# base_circuit.net
KiCad netlist of a schematic drawn in EAGLE
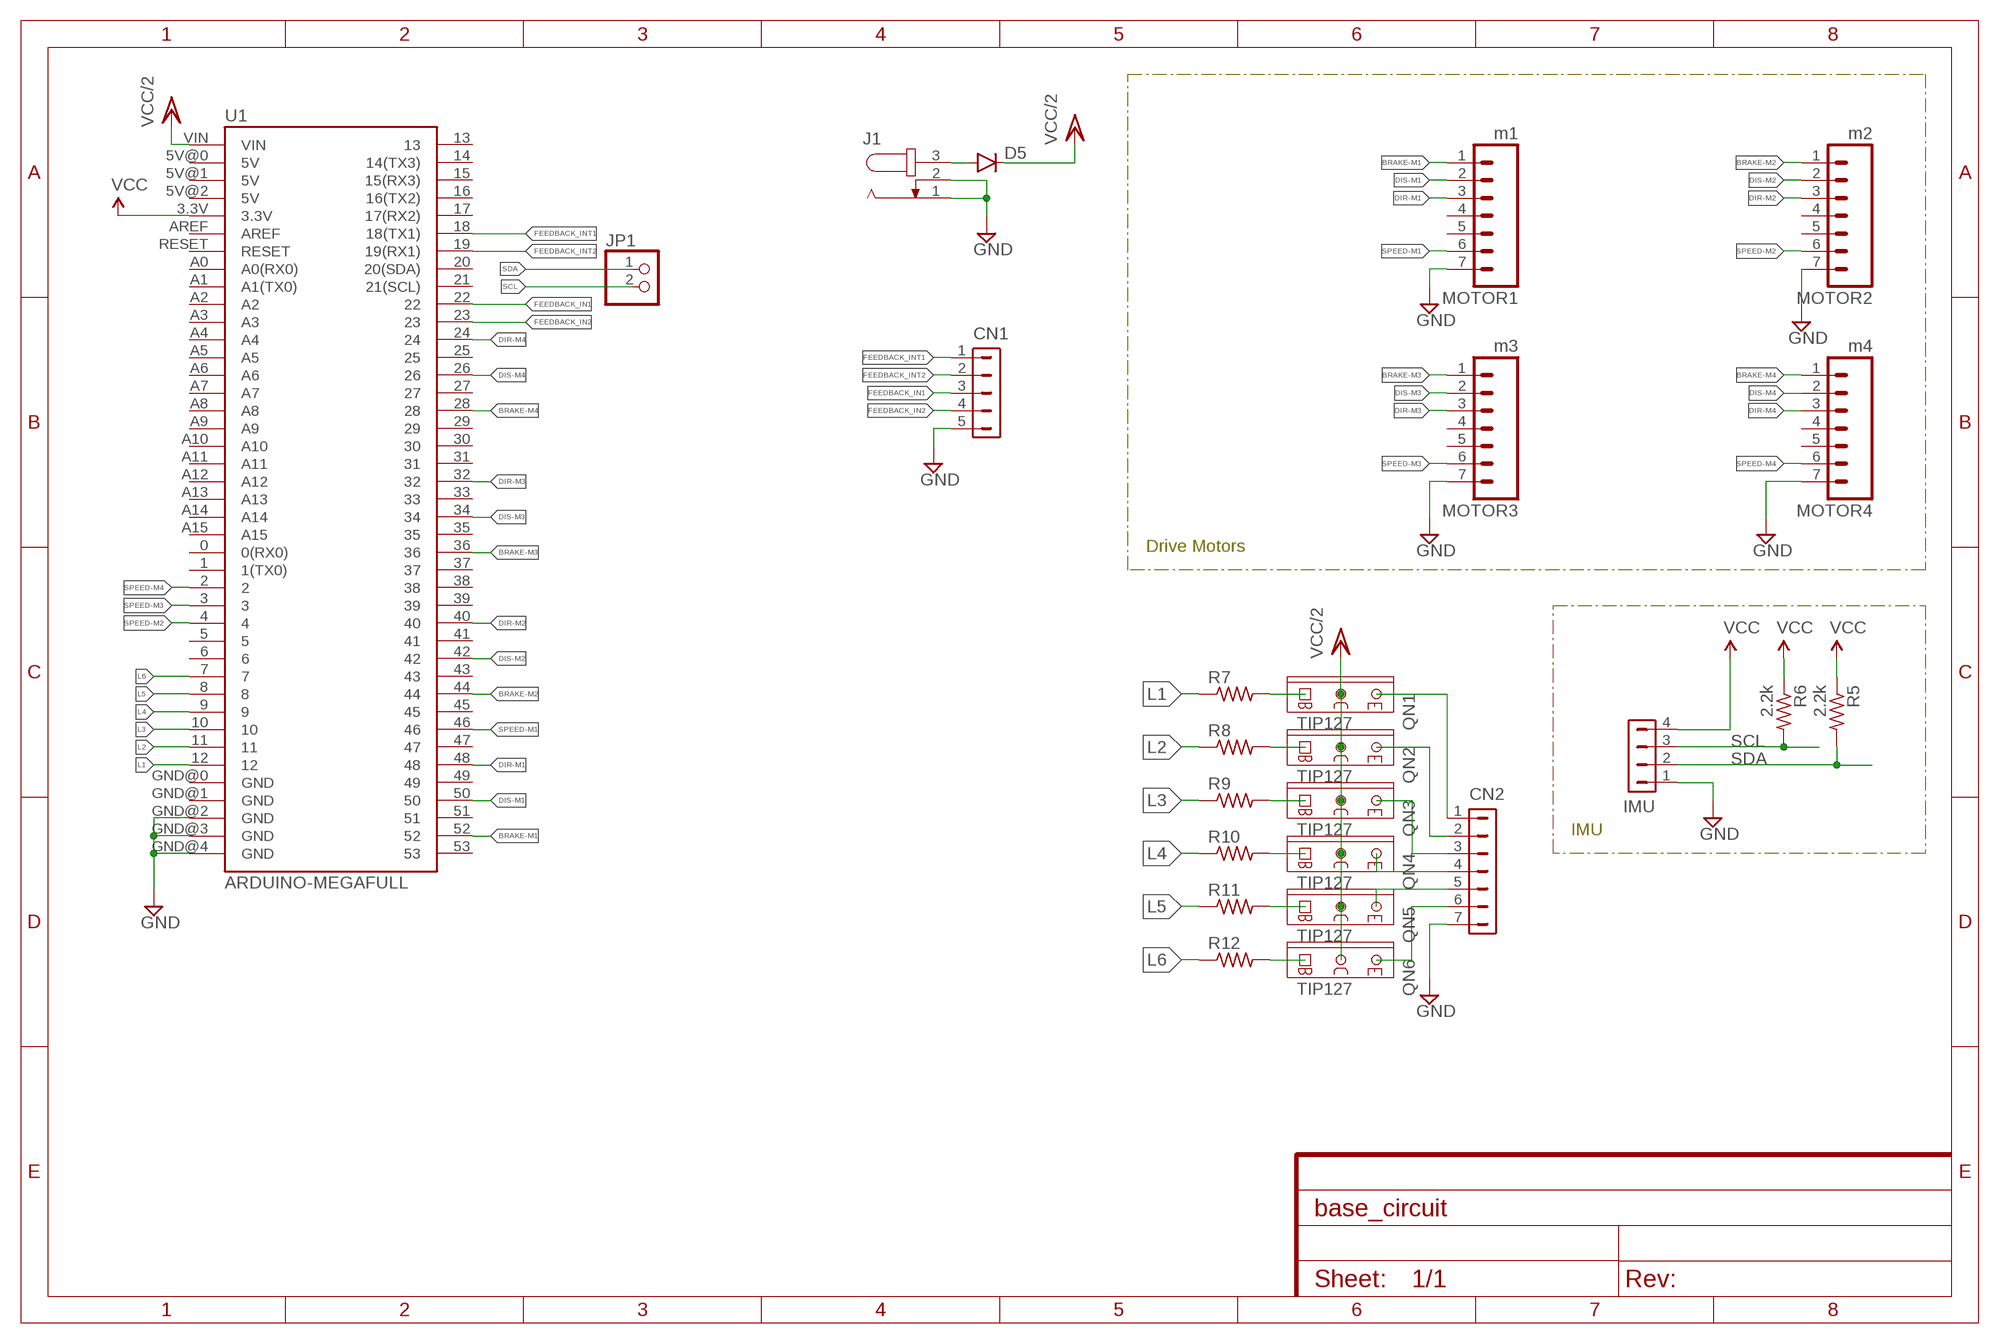
[diagram p0: schematic, sheet 1]

(export (version "E")
  (design (tool "Eeschema 10.0.6"))
  (components
    (comp (ref "CN1")
      (value "HDR-1X5-MTE-100-L")
      (footprint "eagle-import:MTE-100-5VL")
      (libsource (lib "eagle-import") (part "HDR-1X5-MTE-100-L"))
    )
    (comp (ref "CN2")
      (value "HDR-1X7-70543-?")
      (footprint "eagle-import:70543-07")
      (libsource (lib "eagle-import") (part "HDR-1X7-70543-?"))
    )
    (comp (ref "D5")
      (value "DIODEPTH")
      (footprint "eagle-import:DIODE-1N4001")
      (libsource (lib "eagle-import") (part "DIODEPTH"))
    )
    (comp (ref "IMU")
      (value "HDR-1X4-70543-?")
      (footprint "eagle-import:70543-04")
      (libsource (lib "eagle-import") (part "HDR-1X4-70543-?"))
    )
    (comp (ref "J1")
      (value "JACK-PLUG1")
      (footprint "eagle-import:SPC4078")
      (libsource (lib "eagle-import") (part "JACK-PLUG1"))
    )
    (comp (ref "JP1")
      (value "PINHD-1X2")
      (footprint "eagle-import:1X02")
      (libsource (lib "eagle-import") (part "PINHD-1X2"))
    )
    (comp (ref "MOTOR1")
      (value "m1")
      (footprint "eagle-import:07P")
      (libsource (lib "eagle-import") (part "M07"))
    )
    (comp (ref "MOTOR2")
      (value "m2")
      (footprint "eagle-import:07P")
      (libsource (lib "eagle-import") (part "M07"))
    )
    (comp (ref "MOTOR3")
      (value "m3")
      (footprint "eagle-import:07P")
      (libsource (lib "eagle-import") (part "M07"))
    )
    (comp (ref "MOTOR4")
      (value "m4")
      (footprint "eagle-import:07P")
      (libsource (lib "eagle-import") (part "M07"))
    )
    (comp (ref "QN1")
      (value "TIP127")
      (footprint "eagle-import:TO220AV")
      (libsource (lib "eagle-import") (part "TIP127"))
    )
    (comp (ref "QN2")
      (value "TIP127")
      (footprint "eagle-import:TO220AV")
      (libsource (lib "eagle-import") (part "TIP127"))
    )
    (comp (ref "QN3")
      (value "TIP127")
      (footprint "eagle-import:TO220AV")
      (libsource (lib "eagle-import") (part "TIP127"))
    )
    (comp (ref "QN4")
      (value "TIP127")
      (footprint "eagle-import:TO220AV")
      (libsource (lib "eagle-import") (part "TIP127"))
    )
    (comp (ref "QN5")
      (value "TIP127")
      (footprint "eagle-import:TO220AV")
      (libsource (lib "eagle-import") (part "TIP127"))
    )
    (comp (ref "QN6")
      (value "TIP127")
      (footprint "eagle-import:TO220AV")
      (libsource (lib "eagle-import") (part "TIP127"))
    )
    (comp (ref "R5")
      (value "2.2k")
      (footprint "eagle-import:0204_7")
      (libsource (lib "eagle-import") (part "R-US_0204/7"))
    )
    (comp (ref "R6")
      (value "2.2k")
      (footprint "eagle-import:0204_7")
      (libsource (lib "eagle-import") (part "R-US_0204/7"))
    )
    (comp (ref "R7")
      (value "R-US_0207/10")
      (footprint "eagle-import:0207_10")
      (libsource (lib "eagle-import") (part "R-US_0207/10"))
    )
    (comp (ref "R8")
      (value "R-US_0207/10")
      (footprint "eagle-import:0207_10")
      (libsource (lib "eagle-import") (part "R-US_0207/10"))
    )
    (comp (ref "R9")
      (value "R-US_0207/10")
      (footprint "eagle-import:0207_10")
      (libsource (lib "eagle-import") (part "R-US_0207/10"))
    )
    (comp (ref "R10")
      (value "R-US_0207/10")
      (footprint "eagle-import:0207_10")
      (libsource (lib "eagle-import") (part "R-US_0207/10"))
    )
    (comp (ref "R11")
      (value "R-US_0207/10")
      (footprint "eagle-import:0207_10")
      (libsource (lib "eagle-import") (part "R-US_0207/10"))
    )
    (comp (ref "R12")
      (value "R-US_0207/10")
      (footprint "eagle-import:0207_10")
      (libsource (lib "eagle-import") (part "R-US_0207/10"))
    )
    (comp (ref "U1")
      (value "ARDUINO-MEGAFULL")
      (footprint "eagle-import:ARDUINO_MEGA")
      (libsource (lib "eagle-import") (part "ARDUINO-MEGAFULL"))
    )
  )
  (nets
    (net (code "1") (name "BRAKE-M1") (class "Default")
      (node (ref "MOTOR1") (pin "1") (pinfunction "1_1") (pintype "passive"))
      (node (ref "U1") (pin "52") (pinfunction "52_52") (pintype "bidirectional"))
    )
    (net (code "2") (name "BRAKE-M2") (class "Default")
      (node (ref "MOTOR2") (pin "1") (pinfunction "1_1") (pintype "passive"))
      (node (ref "U1") (pin "44") (pinfunction "44_44") (pintype "bidirectional"))
    )
    (net (code "3") (name "BRAKE-M3") (class "Default")
      (node (ref "MOTOR3") (pin "1") (pinfunction "1_1") (pintype "passive"))
      (node (ref "U1") (pin "36") (pinfunction "36_36") (pintype "bidirectional"))
    )
    (net (code "4") (name "BRAKE-M4") (class "Default")
      (node (ref "MOTOR4") (pin "1") (pinfunction "1_1") (pintype "passive"))
      (node (ref "U1") (pin "28") (pinfunction "28_28") (pintype "bidirectional"))
    )
    (net (code "5") (name "DIR-M1") (class "Default")
      (node (ref "MOTOR1") (pin "3") (pinfunction "3_3") (pintype "passive"))
      (node (ref "U1") (pin "48") (pinfunction "48_48") (pintype "bidirectional"))
    )
    (net (code "6") (name "DIR-M2") (class "Default")
      (node (ref "MOTOR2") (pin "3") (pinfunction "3_3") (pintype "passive"))
      (node (ref "U1") (pin "40") (pinfunction "40_40") (pintype "bidirectional"))
    )
    (net (code "7") (name "DIR-M3") (class "Default")
      (node (ref "MOTOR3") (pin "3") (pinfunction "3_3") (pintype "passive"))
      (node (ref "U1") (pin "32") (pinfunction "32_32") (pintype "bidirectional"))
    )
    (net (code "8") (name "DIR-M4") (class "Default")
      (node (ref "MOTOR4") (pin "3") (pinfunction "3_3") (pintype "passive"))
      (node (ref "U1") (pin "24") (pinfunction "24_24") (pintype "bidirectional"))
    )
    (net (code "9") (name "DIS-M1") (class "Default")
      (node (ref "MOTOR1") (pin "2") (pinfunction "2_2") (pintype "passive"))
      (node (ref "U1") (pin "50") (pinfunction "50_50") (pintype "bidirectional"))
    )
    (net (code "10") (name "DIS-M2") (class "Default")
      (node (ref "MOTOR2") (pin "2") (pinfunction "2_2") (pintype "passive"))
      (node (ref "U1") (pin "42") (pinfunction "42_42") (pintype "bidirectional"))
    )
    (net (code "11") (name "DIS-M3") (class "Default")
      (node (ref "MOTOR3") (pin "2") (pinfunction "2_2") (pintype "passive"))
      (node (ref "U1") (pin "34") (pinfunction "34_34") (pintype "bidirectional"))
    )
    (net (code "12") (name "DIS-M4") (class "Default")
      (node (ref "MOTOR4") (pin "2") (pinfunction "2_2") (pintype "passive"))
      (node (ref "U1") (pin "26") (pinfunction "26_26") (pintype "bidirectional"))
    )
    (net (code "13") (name "FEEDBACK_IN1") (class "Default")
      (node (ref "CN1") (pin "3") (pinfunction "3_3") (pintype "passive"))
      (node (ref "U1") (pin "22") (pinfunction "22_22") (pintype "bidirectional"))
    )
    (net (code "14") (name "FEEDBACK_IN2") (class "Default")
      (node (ref "CN1") (pin "4") (pinfunction "4_4") (pintype "passive"))
      (node (ref "U1") (pin "23") (pinfunction "23_23") (pintype "bidirectional"))
    )
    (net (code "15") (name "FEEDBACK_INT1") (class "Default")
      (node (ref "CN1") (pin "1") (pinfunction "1_1") (pintype "passive"))
      (node (ref "U1") (pin "18") (pinfunction "18(TX1)_18") (pintype "bidirectional"))
    )
    (net (code "16") (name "FEEDBACK_INT2") (class "Default")
      (node (ref "CN1") (pin "2") (pinfunction "2_2") (pintype "passive"))
      (node (ref "U1") (pin "19") (pinfunction "19(RX1)_19") (pintype "bidirectional"))
    )
    (net (code "17") (name "GND") (class "Default")
      (node (ref "CN1") (pin "5") (pinfunction "5_5") (pintype "passive"))
      (node (ref "CN2") (pin "7") (pinfunction "7_7") (pintype "passive"))
      (node (ref "IMU") (pin "1") (pinfunction "1_1") (pintype "passive"))
      (node (ref "J1") (pin "1") (pinfunction "1_1") (pintype "passive"))
      (node (ref "J1") (pin "2") (pinfunction "2_2") (pintype "passive"))
      (node (ref "MOTOR1") (pin "7") (pinfunction "7_7") (pintype "passive"))
      (node (ref "MOTOR2") (pin "7") (pinfunction "7_7") (pintype "passive"))
      (node (ref "MOTOR3") (pin "7") (pinfunction "7_7") (pintype "passive"))
      (node (ref "MOTOR4") (pin "7") (pinfunction "7_7") (pintype "passive"))
      (node (ref "U1") (pin "GND@2") (pinfunction "GND_GND@2") (pintype "bidirectional"))
      (node (ref "U1") (pin "GND@3") (pinfunction "GND_GND@3") (pintype "bidirectional"))
      (node (ref "U1") (pin "GND@4") (pinfunction "GND_GND@4") (pintype "bidirectional"))
    )
    (net (code "18") (name "L1") (class "Default")
      (node (ref "R7") (pin "1") (pinfunction "1_1") (pintype "passive"))
      (node (ref "U1") (pin "12") (pinfunction "12_12") (pintype "bidirectional"))
    )
    (net (code "19") (name "L2") (class "Default")
      (node (ref "R8") (pin "1") (pinfunction "1_1") (pintype "passive"))
      (node (ref "U1") (pin "11") (pinfunction "11_11") (pintype "bidirectional"))
    )
    (net (code "20") (name "L3") (class "Default")
      (node (ref "R9") (pin "1") (pinfunction "1_1") (pintype "passive"))
      (node (ref "U1") (pin "10") (pinfunction "10_10") (pintype "bidirectional"))
    )
    (net (code "21") (name "L4") (class "Default")
      (node (ref "R10") (pin "1") (pinfunction "1_1") (pintype "passive"))
      (node (ref "U1") (pin "9") (pinfunction "9_9") (pintype "bidirectional"))
    )
    (net (code "22") (name "L5") (class "Default")
      (node (ref "R11") (pin "1") (pinfunction "1_1") (pintype "passive"))
      (node (ref "U1") (pin "8") (pinfunction "8_8") (pintype "bidirectional"))
    )
    (net (code "23") (name "L6") (class "Default")
      (node (ref "R12") (pin "1") (pinfunction "1_1") (pintype "passive"))
      (node (ref "U1") (pin "7") (pinfunction "7_7") (pintype "bidirectional"))
    )
    (net (code "24") (name "Net-(CN2-Pad1)") (class "Default")
      (node (ref "CN2") (pin "1") (pinfunction "1_1") (pintype "passive"))
      (node (ref "QN1") (pin "E") (pinfunction "E_E") (pintype "passive"))
    )
    (net (code "25") (name "Net-(CN2-Pad2)") (class "Default")
      (node (ref "CN2") (pin "2") (pinfunction "2_2") (pintype "passive"))
      (node (ref "QN2") (pin "E") (pinfunction "E_E") (pintype "passive"))
    )
    (net (code "26") (name "Net-(CN2-Pad3)") (class "Default")
      (node (ref "CN2") (pin "3") (pinfunction "3_3") (pintype "passive"))
      (node (ref "QN3") (pin "E") (pinfunction "E_E") (pintype "passive"))
    )
    (net (code "27") (name "Net-(CN2-Pad4)") (class "Default")
      (node (ref "CN2") (pin "4") (pinfunction "4_4") (pintype "passive"))
      (node (ref "QN4") (pin "E") (pinfunction "E_E") (pintype "passive"))
    )
    (net (code "28") (name "Net-(CN2-Pad5)") (class "Default")
      (node (ref "CN2") (pin "5") (pinfunction "5_5") (pintype "passive"))
      (node (ref "QN5") (pin "E") (pinfunction "E_E") (pintype "passive"))
    )
    (net (code "29") (name "Net-(CN2-Pad6)") (class "Default")
      (node (ref "CN2") (pin "6") (pinfunction "6_6") (pintype "passive"))
      (node (ref "QN6") (pin "E") (pinfunction "E_E") (pintype "passive"))
    )
    (net (code "30") (name "Net-(D5-PadA)") (class "Default")
      (node (ref "D5") (pin "A") (pinfunction "A_A") (pintype "passive"))
      (node (ref "J1") (pin "3") (pinfunction "3_3") (pintype "passive"))
    )
    (net (code "31") (name "Net-(QN1-PadB)") (class "Default")
      (node (ref "QN1") (pin "B") (pinfunction "B_B") (pintype "passive"))
      (node (ref "R7") (pin "2") (pinfunction "2_2") (pintype "passive"))
    )
    (net (code "32") (name "Net-(QN2-PadB)") (class "Default")
      (node (ref "QN2") (pin "B") (pinfunction "B_B") (pintype "passive"))
      (node (ref "R8") (pin "2") (pinfunction "2_2") (pintype "passive"))
    )
    (net (code "33") (name "Net-(QN3-PadB)") (class "Default")
      (node (ref "QN3") (pin "B") (pinfunction "B_B") (pintype "passive"))
      (node (ref "R9") (pin "2") (pinfunction "2_2") (pintype "passive"))
    )
    (net (code "34") (name "Net-(QN4-PadB)") (class "Default")
      (node (ref "QN4") (pin "B") (pinfunction "B_B") (pintype "passive"))
      (node (ref "R10") (pin "2") (pinfunction "2_2") (pintype "passive"))
    )
    (net (code "35") (name "Net-(QN5-PadB)") (class "Default")
      (node (ref "QN5") (pin "B") (pinfunction "B_B") (pintype "passive"))
      (node (ref "R11") (pin "2") (pinfunction "2_2") (pintype "passive"))
    )
    (net (code "36") (name "Net-(QN6-PadB)") (class "Default")
      (node (ref "QN6") (pin "B") (pinfunction "B_B") (pintype "passive"))
      (node (ref "R12") (pin "2") (pinfunction "2_2") (pintype "passive"))
    )
    (net (code "37") (name "SCL") (class "Default")
      (node (ref "IMU") (pin "3") (pinfunction "3_3") (pintype "passive"))
      (node (ref "JP1") (pin "2") (pinfunction "2_2") (pintype "passive"))
      (node (ref "R6") (pin "2") (pinfunction "2_2") (pintype "passive"))
    )
    (net (code "38") (name "SDA") (class "Default")
      (node (ref "IMU") (pin "2") (pinfunction "2_2") (pintype "passive"))
      (node (ref "JP1") (pin "1") (pinfunction "1_1") (pintype "passive"))
      (node (ref "R5") (pin "2") (pinfunction "2_2") (pintype "passive"))
    )
    (net (code "39") (name "SPEED-M1") (class "Default")
      (node (ref "MOTOR1") (pin "6") (pinfunction "6_6") (pintype "passive"))
      (node (ref "U1") (pin "46") (pinfunction "46_46") (pintype "bidirectional"))
    )
    (net (code "40") (name "SPEED-M2") (class "Default")
      (node (ref "MOTOR2") (pin "6") (pinfunction "6_6") (pintype "passive"))
      (node (ref "U1") (pin "4") (pinfunction "4_4") (pintype "bidirectional"))
    )
    (net (code "41") (name "SPEED-M3") (class "Default")
      (node (ref "MOTOR3") (pin "6") (pinfunction "6_6") (pintype "passive"))
      (node (ref "U1") (pin "3") (pinfunction "3_3") (pintype "bidirectional"))
    )
    (net (code "42") (name "SPEED-M4") (class "Default")
      (node (ref "MOTOR4") (pin "6") (pinfunction "6_6") (pintype "passive"))
      (node (ref "U1") (pin "2") (pinfunction "2_2") (pintype "bidirectional"))
    )
    (net (code "43") (name "VCC") (class "Default")
      (node (ref "IMU") (pin "4") (pinfunction "4_4") (pintype "passive"))
      (node (ref "R5") (pin "1") (pinfunction "1_1") (pintype "passive"))
      (node (ref "R6") (pin "1") (pinfunction "1_1") (pintype "passive"))
      (node (ref "U1") (pin "3.3V") (pinfunction "3.3V_3.3V") (pintype "bidirectional"))
    )
    (net (code "44") (name "VCC{slash}2") (class "Default")
      (node (ref "D5") (pin "C") (pinfunction "C_C") (pintype "passive"))
      (node (ref "QN1") (pin "C") (pinfunction "C_C") (pintype "passive"))
      (node (ref "QN2") (pin "C") (pinfunction "C_C") (pintype "passive"))
      (node (ref "QN3") (pin "C") (pinfunction "C_C") (pintype "passive"))
      (node (ref "QN4") (pin "C") (pinfunction "C_C") (pintype "passive"))
      (node (ref "QN5") (pin "C") (pinfunction "C_C") (pintype "passive"))
      (node (ref "QN6") (pin "C") (pinfunction "C_C") (pintype "passive"))
      (node (ref "U1") (pin "VIN") (pinfunction "VIN_VIN") (pintype "bidirectional"))
    )
    (net (code "45") (name "unconnected-(MOTOR1-Pad4)") (class "Default")
      (node (ref "MOTOR1") (pin "4") (pinfunction "4_4") (pintype "passive"))
    )
    (net (code "46") (name "unconnected-(MOTOR1-Pad5)") (class "Default")
      (node (ref "MOTOR1") (pin "5") (pinfunction "5_5") (pintype "passive"))
    )
    (net (code "47") (name "unconnected-(MOTOR2-Pad4)") (class "Default")
      (node (ref "MOTOR2") (pin "4") (pinfunction "4_4") (pintype "passive"))
    )
    (net (code "48") (name "unconnected-(MOTOR2-Pad5)") (class "Default")
      (node (ref "MOTOR2") (pin "5") (pinfunction "5_5") (pintype "passive"))
    )
    (net (code "49") (name "unconnected-(MOTOR3-Pad4)") (class "Default")
      (node (ref "MOTOR3") (pin "4") (pinfunction "4_4") (pintype "passive"))
    )
    (net (code "50") (name "unconnected-(MOTOR3-Pad5)") (class "Default")
      (node (ref "MOTOR3") (pin "5") (pinfunction "5_5") (pintype "passive"))
    )
    (net (code "51") (name "unconnected-(MOTOR4-Pad4)") (class "Default")
      (node (ref "MOTOR4") (pin "4") (pinfunction "4_4") (pintype "passive"))
    )
    (net (code "52") (name "unconnected-(MOTOR4-Pad5)") (class "Default")
      (node (ref "MOTOR4") (pin "5") (pinfunction "5_5") (pintype "passive"))
    )
    (net (code "53") (name "unconnected-(U1-0(RX0)-Pad0)") (class "Default")
      (node (ref "U1") (pin "0") (pinfunction "0(RX0)_0") (pintype "bidirectional"))
    )
    (net (code "54") (name "unconnected-(U1-1(TX0)-Pad1)") (class "Default")
      (node (ref "U1") (pin "1") (pinfunction "1(TX0)_1") (pintype "bidirectional"))
    )
    (net (code "55") (name "unconnected-(U1-5V-Pad5V@0)") (class "Default")
      (node (ref "U1") (pin "5V@0") (pinfunction "5V_5V@0") (pintype "bidirectional"))
    )
    (net (code "56") (name "unconnected-(U1-5V-Pad5V@1)") (class "Default")
      (node (ref "U1") (pin "5V@1") (pinfunction "5V_5V@1") (pintype "bidirectional"))
    )
    (net (code "57") (name "unconnected-(U1-5V-Pad5V@2)") (class "Default")
      (node (ref "U1") (pin "5V@2") (pinfunction "5V_5V@2") (pintype "bidirectional"))
    )
    (net (code "58") (name "unconnected-(U1-14(TX3)-Pad14)") (class "Default")
      (node (ref "U1") (pin "14") (pinfunction "14(TX3)_14") (pintype "bidirectional"))
    )
    (net (code "59") (name "unconnected-(U1-15(RX3)-Pad15)") (class "Default")
      (node (ref "U1") (pin "15") (pinfunction "15(RX3)_15") (pintype "bidirectional"))
    )
    (net (code "60") (name "unconnected-(U1-16(TX2)-Pad16)") (class "Default")
      (node (ref "U1") (pin "16") (pinfunction "16(TX2)_16") (pintype "bidirectional"))
    )
    (net (code "61") (name "unconnected-(U1-17(RX2)-Pad17)") (class "Default")
      (node (ref "U1") (pin "17") (pinfunction "17(RX2)_17") (pintype "bidirectional"))
    )
    (net (code "62") (name "unconnected-(U1-20(SDA)-Pad20)") (class "Default")
      (node (ref "U1") (pin "20") (pinfunction "20(SDA)_20") (pintype "bidirectional"))
    )
    (net (code "63") (name "unconnected-(U1-21(SCL)-Pad21)") (class "Default")
      (node (ref "U1") (pin "21") (pinfunction "21(SCL)_21") (pintype "bidirectional"))
    )
    (net (code "64") (name "unconnected-(U1-A0(RX0)-PadA0)") (class "Default")
      (node (ref "U1") (pin "A0") (pinfunction "A0(RX0)_A0") (pintype "bidirectional"))
    )
    (net (code "65") (name "unconnected-(U1-A1(TX0)-PadA1)") (class "Default")
      (node (ref "U1") (pin "A1") (pinfunction "A1(TX0)_A1") (pintype "bidirectional"))
    )
    (net (code "66") (name "unconnected-(U1-GND-PadGND@0)") (class "Default")
      (node (ref "U1") (pin "GND@0") (pinfunction "GND_GND@0") (pintype "bidirectional"))
    )
    (net (code "67") (name "unconnected-(U1-GND-PadGND@1)") (class "Default")
      (node (ref "U1") (pin "GND@1") (pinfunction "GND_GND@1") (pintype "bidirectional"))
    )
    (net (code "68") (name "unconnected-(U1-Pad5)") (class "Default")
      (node (ref "U1") (pin "5") (pinfunction "5_5") (pintype "bidirectional"))
    )
    (net (code "69") (name "unconnected-(U1-Pad6)") (class "Default")
      (node (ref "U1") (pin "6") (pinfunction "6_6") (pintype "bidirectional"))
    )
    (net (code "70") (name "unconnected-(U1-Pad13)") (class "Default")
      (node (ref "U1") (pin "13") (pinfunction "13_13") (pintype "bidirectional"))
    )
    (net (code "71") (name "unconnected-(U1-Pad25)") (class "Default")
      (node (ref "U1") (pin "25") (pinfunction "25_25") (pintype "bidirectional"))
    )
    (net (code "72") (name "unconnected-(U1-Pad27)") (class "Default")
      (node (ref "U1") (pin "27") (pinfunction "27_27") (pintype "bidirectional"))
    )
    (net (code "73") (name "unconnected-(U1-Pad29)") (class "Default")
      (node (ref "U1") (pin "29") (pinfunction "29_29") (pintype "bidirectional"))
    )
    (net (code "74") (name "unconnected-(U1-Pad30)") (class "Default")
      (node (ref "U1") (pin "30") (pinfunction "30_30") (pintype "bidirectional"))
    )
    (net (code "75") (name "unconnected-(U1-Pad31)") (class "Default")
      (node (ref "U1") (pin "31") (pinfunction "31_31") (pintype "bidirectional"))
    )
    (net (code "76") (name "unconnected-(U1-Pad33)") (class "Default")
      (node (ref "U1") (pin "33") (pinfunction "33_33") (pintype "bidirectional"))
    )
    (net (code "77") (name "unconnected-(U1-Pad35)") (class "Default")
      (node (ref "U1") (pin "35") (pinfunction "35_35") (pintype "bidirectional"))
    )
    (net (code "78") (name "unconnected-(U1-Pad37)") (class "Default")
      (node (ref "U1") (pin "37") (pinfunction "37_37") (pintype "bidirectional"))
    )
    (net (code "79") (name "unconnected-(U1-Pad38)") (class "Default")
      (node (ref "U1") (pin "38") (pinfunction "38_38") (pintype "bidirectional"))
    )
    (net (code "80") (name "unconnected-(U1-Pad39)") (class "Default")
      (node (ref "U1") (pin "39") (pinfunction "39_39") (pintype "bidirectional"))
    )
    (net (code "81") (name "unconnected-(U1-Pad41)") (class "Default")
      (node (ref "U1") (pin "41") (pinfunction "41_41") (pintype "bidirectional"))
    )
    (net (code "82") (name "unconnected-(U1-Pad43)") (class "Default")
      (node (ref "U1") (pin "43") (pinfunction "43_43") (pintype "bidirectional"))
    )
    (net (code "83") (name "unconnected-(U1-Pad45)") (class "Default")
      (node (ref "U1") (pin "45") (pinfunction "45_45") (pintype "bidirectional"))
    )
    (net (code "84") (name "unconnected-(U1-Pad47)") (class "Default")
      (node (ref "U1") (pin "47") (pinfunction "47_47") (pintype "bidirectional"))
    )
    (net (code "85") (name "unconnected-(U1-Pad49)") (class "Default")
      (node (ref "U1") (pin "49") (pinfunction "49_49") (pintype "bidirectional"))
    )
    (net (code "86") (name "unconnected-(U1-Pad51)") (class "Default")
      (node (ref "U1") (pin "51") (pinfunction "51_51") (pintype "bidirectional"))
    )
    (net (code "87") (name "unconnected-(U1-Pad53)") (class "Default")
      (node (ref "U1") (pin "53") (pinfunction "53_53") (pintype "bidirectional"))
    )
    (net (code "88") (name "unconnected-(U1-PadA2)") (class "Default")
      (node (ref "U1") (pin "A2") (pinfunction "A2_A2") (pintype "bidirectional"))
    )
    (net (code "89") (name "unconnected-(U1-PadA3)") (class "Default")
      (node (ref "U1") (pin "A3") (pinfunction "A3_A3") (pintype "bidirectional"))
    )
    (net (code "90") (name "unconnected-(U1-PadA4)") (class "Default")
      (node (ref "U1") (pin "A4") (pinfunction "A4_A4") (pintype "bidirectional"))
    )
    (net (code "91") (name "unconnected-(U1-PadA5)") (class "Default")
      (node (ref "U1") (pin "A5") (pinfunction "A5_A5") (pintype "bidirectional"))
    )
    (net (code "92") (name "unconnected-(U1-PadA6)") (class "Default")
      (node (ref "U1") (pin "A6") (pinfunction "A6_A6") (pintype "bidirectional"))
    )
    (net (code "93") (name "unconnected-(U1-PadA7)") (class "Default")
      (node (ref "U1") (pin "A7") (pinfunction "A7_A7") (pintype "bidirectional"))
    )
    (net (code "94") (name "unconnected-(U1-PadA8)") (class "Default")
      (node (ref "U1") (pin "A8") (pinfunction "A8_A8") (pintype "bidirectional"))
    )
    (net (code "95") (name "unconnected-(U1-PadA9)") (class "Default")
      (node (ref "U1") (pin "A9") (pinfunction "A9_A9") (pintype "bidirectional"))
    )
    (net (code "96") (name "unconnected-(U1-PadA10)") (class "Default")
      (node (ref "U1") (pin "A10") (pinfunction "A10_A10") (pintype "bidirectional"))
    )
    (net (code "97") (name "unconnected-(U1-PadA11)") (class "Default")
      (node (ref "U1") (pin "A11") (pinfunction "A11_A11") (pintype "bidirectional"))
    )
    (net (code "98") (name "unconnected-(U1-PadA12)") (class "Default")
      (node (ref "U1") (pin "A12") (pinfunction "A12_A12") (pintype "bidirectional"))
    )
    (net (code "99") (name "unconnected-(U1-PadA13)") (class "Default")
      (node (ref "U1") (pin "A13") (pinfunction "A13_A13") (pintype "bidirectional"))
    )
    (net (code "100") (name "unconnected-(U1-PadA14)") (class "Default")
      (node (ref "U1") (pin "A14") (pinfunction "A14_A14") (pintype "bidirectional"))
    )
    (net (code "101") (name "unconnected-(U1-PadA15)") (class "Default")
      (node (ref "U1") (pin "A15") (pinfunction "A15_A15") (pintype "bidirectional"))
    )
    (net (code "102") (name "unconnected-(U1-PadAREF)") (class "Default")
      (node (ref "U1") (pin "AREF") (pinfunction "AREF_AREF") (pintype "bidirectional"))
    )
    (net (code "103") (name "unconnected-(U1-PadRESET)") (class "Default")
      (node (ref "U1") (pin "RESET") (pinfunction "RESET_RESET") (pintype "bidirectional"))
    )
  )
)
